# ESP32.net
KiCad netlist of a schematic drawn in Altium Designer
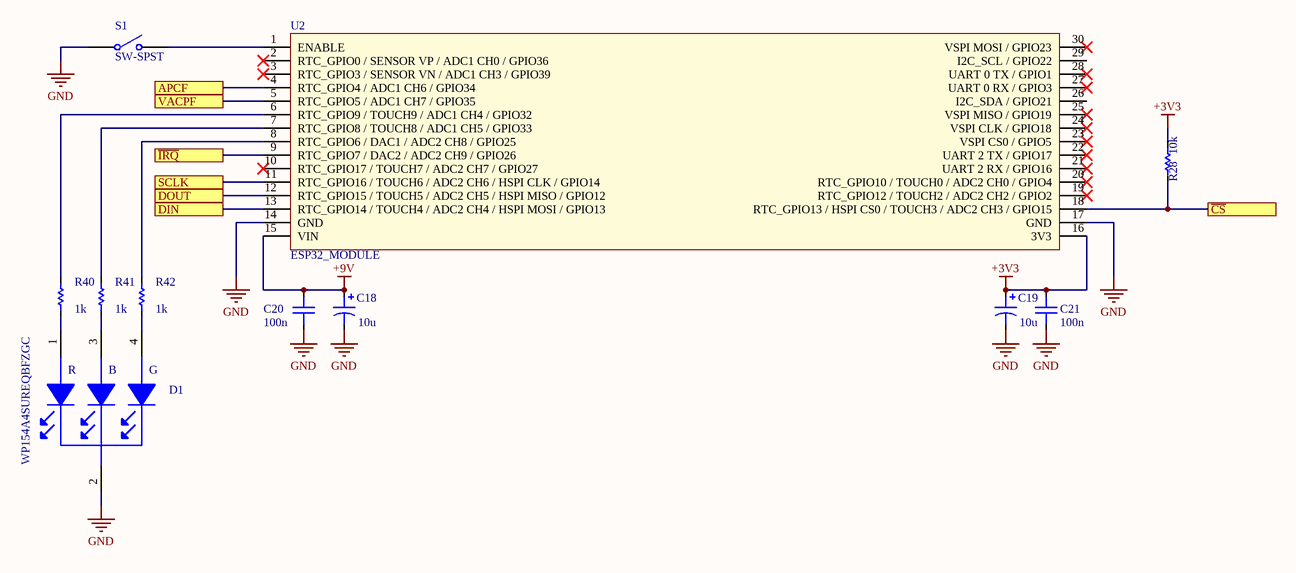
[diagram p0: ESP32.SchDoc]

(export (version "E")
  (design (tool "Eeschema 10.0.6"))
  (components
    (comp (ref "C18")
      (value "10u")
      (footprint "CAP1210 - TANTALUM")
      (description "Capacitor Polarizado")
      (fields (field (name "Comment") "Capacitor"))
      (libsource (lib "Simbolos") (part "Capacitor Polarizado"))
    )
    (comp (ref "C19")
      (value "10u")
      (footprint "CAP1210 - TANTALUM")
      (description "Capacitor Polarizado")
      (fields (field (name "Comment") "Capacitor"))
      (libsource (lib "Simbolos") (part "Capacitor Polarizado"))
    )
    (comp (ref "C20")
      (value "100n")
      (footprint "CAP0603")
      (description "Capacitor")
      (libsource (lib "Simbolos") (part "Capacitor"))
    )
    (comp (ref "C21")
      (value "100n")
      (footprint "CAP0603")
      (description "Capacitor")
      (libsource (lib "Simbolos") (part "Capacitor"))
    )
    (comp (ref "D1")
      (value "WP154A4SUREQBFZGC")
      (footprint "HDR1X4")
      (fields (field (name "MANUFACTURER") "Kingbright"))
      (libsource (lib "PLUS5_CPQD") (part "LED RGB K"))
    )
    (comp (ref "R28")
      (value "10k")
      (footprint "RES0603")
      (description "Resistor")
      (libsource (lib "Simbolos") (part "Resistor"))
    )
    (comp (ref "R40")
      (value "1k")
      (footprint "RES0603")
      (description "Resistor")
      (libsource (lib "Simbolos") (part "Resistor"))
    )
    (comp (ref "R41")
      (value "1k")
      (footprint "RES0603")
      (description "Resistor")
      (libsource (lib "Simbolos") (part "Resistor"))
    )
    (comp (ref "R42")
      (value "1k")
      (footprint "RES0603")
      (description "Resistor")
      (libsource (lib "Simbolos") (part "Resistor"))
    )
    (comp (ref "S1")
      (value "SW-SPST")
      (footprint "HDR1X2")
      (description "Single-Pole, Single-Throw Switch")
      (fields (field (name "PUBLISHER") "Altium Limited"))
      (libsource (lib "Miscellaneous Devices") (part "SW-SPST"))
    )
    (comp (ref "U2")
      (value "ESP32_MODULE")
      (footprint "ESP32 DEVKIT V1 DOIT")
      (fields (field (name "PART NUMBER") "ESP32_MODULE"))
      (libsource (lib "Simbolos") (part "ESP32_MODULE"))
    )
  )
  (nets
    (net (code "1") (name "+3V3") (class "Default")
      (node (ref "C19") (pin "1") (pinfunction "1_1") (pintype "passive"))
      (node (ref "C21") (pin "2") (pinfunction "2_2") (pintype "passive"))
      (node (ref "R28") (pin "1") (pinfunction "1_1") (pintype "passive"))
      (node (ref "U2") (pin "16") (pinfunction "3V3_16") (pintype "passive"))
    )
    (net (code "2") (name "+9V") (class "Default")
      (node (ref "C18") (pin "1") (pinfunction "1_1") (pintype "passive"))
      (node (ref "C20") (pin "2") (pinfunction "2_2") (pintype "passive"))
      (node (ref "U2") (pin "15") (pinfunction "VIN_15") (pintype "passive"))
    )
    (net (code "3") (name "/APCF") (class "Default")
      (node (ref "U2") (pin "4") (pinfunction "RTC_GPIO4_/_ADC1_CH6_/_GPIO34_4") (pintype "passive"))
    )
    (net (code "4") (name "/DIN") (class "Default")
      (node (ref "U2") (pin "13") (pinfunction "RTC_GPIO14_/_TOUCH4_/_ADC2_CH4_/_HSPI_MOSI_/_GPIO13_13") (pintype "passive"))
    )
    (net (code "5") (name "/DOUT") (class "Default")
      (node (ref "U2") (pin "12") (pinfunction "RTC_GPIO15_/_TOUCH5_/_ADC2_CH5_/_HSPI_MISO_/_GPIO12_12") (pintype "passive"))
    )
    (net (code "6") (name "/SCLK") (class "Default")
      (node (ref "U2") (pin "11") (pinfunction "RTC_GPIO16_/_TOUCH6_/_ADC2_CH6_/_HSPI_CLK_/_GPIO14_11") (pintype "passive"))
    )
    (net (code "7") (name "/VACPF") (class "Default")
      (node (ref "U2") (pin "5") (pinfunction "RTC_GPIO5_/_ADC1_CH7_/_GPIO35_5") (pintype "passive"))
    )
    (net (code "8") (name "/~{CS}") (class "Default")
      (node (ref "R28") (pin "2") (pinfunction "2_2") (pintype "passive"))
      (node (ref "U2") (pin "18") (pinfunction "RTC_GPIO13_/_HSPI_CS0_/_TOUCH3_/_ADC2_CH3_/_GPIO15_18") (pintype "passive"))
    )
    (net (code "9") (name "/~{IRQ}") (class "Default")
      (node (ref "U2") (pin "9") (pinfunction "RTC_GPIO7_/_DAC2_/_ADC2_CH9_/_GPIO26_9") (pintype "passive"))
    )
    (net (code "10") (name "GND") (class "Default")
      (node (ref "C18") (pin "2") (pinfunction "2_2") (pintype "passive"))
      (node (ref "C19") (pin "2") (pinfunction "2_2") (pintype "passive"))
      (node (ref "C20") (pin "1") (pinfunction "1_1") (pintype "passive"))
      (node (ref "C21") (pin "1") (pinfunction "1_1") (pintype "passive"))
      (node (ref "D1") (pin "2") (pinfunction "K_2") (pintype "passive"))
      (node (ref "S1") (pin "1") (pinfunction "COMMON_1") (pintype "passive"))
      (node (ref "U2") (pin "14") (pinfunction "GND_14") (pintype "passive"))
      (node (ref "U2") (pin "17") (pinfunction "GND_17") (pintype "passive"))
    )
    (net (code "11") (name "Net-(D1-A1)") (class "Default")
      (node (ref "D1") (pin "1") (pinfunction "A1_1") (pintype "passive"))
      (node (ref "R40") (pin "2") (pinfunction "2_2") (pintype "passive"))
    )
    (net (code "12") (name "Net-(D1-A2)") (class "Default")
      (node (ref "D1") (pin "3") (pinfunction "A2_3") (pintype "passive"))
      (node (ref "R41") (pin "2") (pinfunction "2_2") (pintype "passive"))
    )
    (net (code "13") (name "Net-(D1-A3)") (class "Default")
      (node (ref "D1") (pin "4") (pinfunction "A3_4") (pintype "passive"))
      (node (ref "R42") (pin "2") (pinfunction "2_2") (pintype "passive"))
    )
    (net (code "14") (name "Net-(S1-NO)") (class "Default")
      (node (ref "S1") (pin "2") (pinfunction "NO_2") (pintype "passive"))
      (node (ref "U2") (pin "1") (pinfunction "ENABLE_1") (pintype "passive"))
    )
    (net (code "15") (name "Net-(U2-RTC_GPIO6_{slash}_DAC1_{slash}_ADC2_CH8_{slash}_GPIO25)") (class "Default")
      (node (ref "R42") (pin "1") (pinfunction "1_1") (pintype "passive"))
      (node (ref "U2") (pin "8") (pinfunction "RTC_GPIO6_/_DAC1_/_ADC2_CH8_/_GPIO25_8") (pintype "passive"))
    )
    (net (code "16") (name "Net-(U2-RTC_GPIO8_{slash}_TOUCH8_{slash}_ADC1_CH5_{slash}_GPIO33)") (class "Default")
      (node (ref "R41") (pin "1") (pinfunction "1_1") (pintype "passive"))
      (node (ref "U2") (pin "7") (pinfunction "RTC_GPIO8_/_TOUCH8_/_ADC1_CH5_/_GPIO33_7") (pintype "passive"))
    )
    (net (code "17") (name "Net-(U2-RTC_GPIO9_{slash}_TOUCH9_{slash}_ADC1_CH4_{slash}_GPIO32)") (class "Default")
      (node (ref "R40") (pin "1") (pinfunction "1_1") (pintype "passive"))
      (node (ref "U2") (pin "6") (pinfunction "RTC_GPIO9_/_TOUCH9_/_ADC1_CH4_/_GPIO32_6") (pintype "passive"))
    )
    (net (code "18") (name "unconnected-(U2-I2C_SCL_{slash}_GPIO22-Pad29)") (class "Default")
      (node (ref "U2") (pin "29") (pinfunction "I2C_SCL_/_GPIO22_29") (pintype "passive"))
    )
    (net (code "19") (name "unconnected-(U2-I2C_SDA_{slash}_GPIO21-Pad26)") (class "Default")
      (node (ref "U2") (pin "26") (pinfunction "I2C_SDA_/_GPIO21_26") (pintype "passive"))
    )
    (net (code "20") (name "unconnected-(U2-RTC_GPIO0_{slash}_SENSOR_VP_{slash}_ADC1_CH0_{slash}_GPIO36-Pad2)") (class "Default")
      (node (ref "U2") (pin "2") (pinfunction "RTC_GPIO0_/_SENSOR_VP_/_ADC1_CH0_/_GPIO36_2") (pintype "passive+no_connect"))
    )
    (net (code "21") (name "unconnected-(U2-RTC_GPIO3_{slash}_SENSOR_VN_{slash}_ADC1_CH3_{slash}_GPIO39-Pad3)") (class "Default")
      (node (ref "U2") (pin "3") (pinfunction "RTC_GPIO3_/_SENSOR_VN_/_ADC1_CH3_/_GPIO39_3") (pintype "passive+no_connect"))
    )
    (net (code "22") (name "unconnected-(U2-RTC_GPIO10_{slash}_TOUCH0_{slash}_ADC2_CH0_{slash}_GPIO4-Pad20)") (class "Default")
      (node (ref "U2") (pin "20") (pinfunction "RTC_GPIO10_/_TOUCH0_/_ADC2_CH0_/_GPIO4_20") (pintype "passive+no_connect"))
    )
    (net (code "23") (name "unconnected-(U2-RTC_GPIO12_{slash}_TOUCH2_{slash}_ADC2_CH2_{slash}_GPIO2-Pad19)") (class "Default")
      (node (ref "U2") (pin "19") (pinfunction "RTC_GPIO12_/_TOUCH2_/_ADC2_CH2_/_GPIO2_19") (pintype "passive+no_connect"))
    )
    (net (code "24") (name "unconnected-(U2-RTC_GPIO17_{slash}_TOUCH7_{slash}_ADC2_CH7_{slash}_GPIO27-Pad10)") (class "Default")
      (node (ref "U2") (pin "10") (pinfunction "RTC_GPIO17_/_TOUCH7_/_ADC2_CH7_/_GPIO27_10") (pintype "passive+no_connect"))
    )
    (net (code "25") (name "unconnected-(U2-UART_0_RX_{slash}_GPIO3-Pad27)") (class "Default")
      (node (ref "U2") (pin "27") (pinfunction "UART_0_RX_/_GPIO3_27") (pintype "passive+no_connect"))
    )
    (net (code "26") (name "unconnected-(U2-UART_0_TX_{slash}_GPIO1-Pad28)") (class "Default")
      (node (ref "U2") (pin "28") (pinfunction "UART_0_TX_/_GPIO1_28") (pintype "passive+no_connect"))
    )
    (net (code "27") (name "unconnected-(U2-UART_2_RX_{slash}_GPIO16-Pad21)") (class "Default")
      (node (ref "U2") (pin "21") (pinfunction "UART_2_RX_/_GPIO16_21") (pintype "passive+no_connect"))
    )
    (net (code "28") (name "unconnected-(U2-UART_2_TX_{slash}_GPIO17-Pad22)") (class "Default")
      (node (ref "U2") (pin "22") (pinfunction "UART_2_TX_/_GPIO17_22") (pintype "passive+no_connect"))
    )
    (net (code "29") (name "unconnected-(U2-VSPI_CLK_{slash}_GPIO18-Pad24)") (class "Default")
      (node (ref "U2") (pin "24") (pinfunction "VSPI_CLK_/_GPIO18_24") (pintype "passive+no_connect"))
    )
    (net (code "30") (name "unconnected-(U2-VSPI_CS0_{slash}_GPIO5-Pad23)") (class "Default")
      (node (ref "U2") (pin "23") (pinfunction "VSPI_CS0_/_GPIO5_23") (pintype "passive+no_connect"))
    )
    (net (code "31") (name "unconnected-(U2-VSPI_MISO_{slash}_GPIO19-Pad25)") (class "Default")
      (node (ref "U2") (pin "25") (pinfunction "VSPI_MISO_/_GPIO19_25") (pintype "passive+no_connect"))
    )
    (net (code "32") (name "unconnected-(U2-VSPI_MOSI_{slash}_GPIO23-Pad30)") (class "Default")
      (node (ref "U2") (pin "30") (pinfunction "VSPI_MOSI_/_GPIO23_30") (pintype "passive+no_connect"))
    )
  )
)
